# 12-.net
KiCad netlist of a schematic drawn in Altium Designer
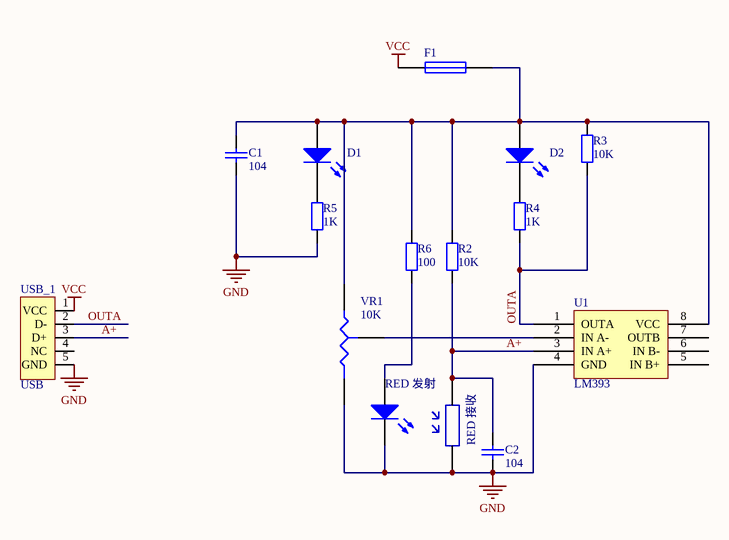
[diagram p0: 12-红外测距及避障原理图.SchDoc]

(export (version "E")
  (design (tool "Eeschema 10.0.6"))
  (components
    (comp (ref "C1")
      (value "104")
      (footprint "0805")
      (description "Capacitor (Semiconductor SIM Model)")
      (fields (field (name "Comment") "Cap Semi") (field (name "PUBLISHER") "Altium Limited"))
      (libsource (lib "Miscellaneous Devices") (part "Cap Semi"))
    )
    (comp (ref "C2")
      (value "104")
      (footprint "0805")
      (description "Capacitor (Semiconductor SIM Model)")
      (fields (field (name "Comment") "Cap Semi") (field (name "PUBLISHER") "Altium Limited"))
      (libsource (lib "Miscellaneous Devices") (part "Cap Semi"))
    )
    (comp (ref "D1")
      (value "LED0")
      (footprint "0805")
      (description "Typical INFRARED GaAs LED")
      (fields (field (name "PUBLISHER") "Altium Limited"))
      (libsource (lib "Miscellaneous Devices") (part "LED0"))
    )
    (comp (ref "D2")
      (value "LED0")
      (footprint "0805")
      (description "Typical INFRARED GaAs LED")
      (fields (field (name "PUBLISHER") "Altium Limited"))
      (libsource (lib "Miscellaneous Devices") (part "LED0"))
    )
    (comp (ref "F1")
      (value "Fuse 1")
      (footprint "Fuse")
      (description "Fuse")
      (fields (field (name "PUBLISHER") "Altium Limited"))
      (libsource (lib "Miscellaneous Devices") (part "Fuse 1"))
    )
    (comp (ref "R2")
      (value "10K")
      (footprint "0805")
      (description "Resistor")
      (fields (field (name "Comment") "Res2") (field (name "PUBLISHER") "Altium Limited"))
      (libsource (lib "Miscellaneous Devices") (part "Res2"))
    )
    (comp (ref "R3")
      (value "10K")
      (footprint "0805")
      (description "Resistor")
      (fields (field (name "Comment") "Res2") (field (name "PUBLISHER") "Altium Limited"))
      (libsource (lib "Miscellaneous Devices") (part "Res2"))
    )
    (comp (ref "R4")
      (value "1K")
      (footprint "0805")
      (description "Resistor")
      (fields (field (name "Comment") "Res2") (field (name "PUBLISHER") "Altium Limited"))
      (libsource (lib "Miscellaneous Devices") (part "Res2"))
    )
    (comp (ref "R5")
      (value "1K")
      (footprint "0805")
      (description "Resistor")
      (fields (field (name "Comment") "Res2") (field (name "PUBLISHER") "Altium Limited"))
      (libsource (lib "Miscellaneous Devices") (part "Res2"))
    )
    (comp (ref "R6")
      (value "100")
      (footprint "0805")
      (description "Resistor")
      (fields (field (name "Comment") "Res2") (field (name "PUBLISHER") "Altium Limited"))
      (libsource (lib "Miscellaneous Devices") (part "Res2"))
    )
    (comp (ref "RED 发射")
      (value "LED0")
      (footprint "LED")
      (description "Typical INFRARED GaAs LED")
      (fields (field (name "PUBLISHER") "Altium Limited"))
      (libsource (lib "Miscellaneous Devices") (part "LED0"))
    )
    (comp (ref "RED 接收") (value "light_resistor") (footprint "LED") (libsource (lib "原理图库") (part "light")))
    (comp (ref "U1") (value "LM393") (footprint "SOP-8") (libsource (lib "原理图库") (part "LM393")))
    (comp (ref "USB_1") (value "USB") (footprint "USB/SM0.8-6H5") (libsource (lib "原理图库") (part "USB5")))
    (comp (ref "VR1")
      (value "10K")
      (footprint "VR")
      (description "Tapped Resistor")
      (fields (field (name "Comment") "Res Tap") (field (name "PUBLISHER") "Altium Limited"))
      (libsource (lib "Miscellaneous Devices") (part "Res Tap"))
    )
  )
  (nets
    (net (code "1") (name "/A+") (class "Default")
      (node (ref "C2") (pin "2") (pinfunction "2_2") (pintype "passive"))
      (node (ref "R2") (pin "1") (pinfunction "1_1") (pintype "passive"))
      (node (ref "RED 接收") (pin "1") (pinfunction "1_1") (pintype "passive"))
      (node (ref "U1") (pin "3") (pinfunction "IN_A+_3") (pintype "passive"))
      (node (ref "USB_1") (pin "3") (pinfunction "D+_3") (pintype "passive"))
    )
    (net (code "2") (name "/OUTA") (class "Default")
      (node (ref "R3") (pin "1") (pinfunction "1_1") (pintype "passive"))
      (node (ref "R4") (pin "1") (pinfunction "1_1") (pintype "passive"))
      (node (ref "U1") (pin "1") (pinfunction "OUTA_1") (pintype "passive"))
      (node (ref "USB_1") (pin "2") (pinfunction "D-_2") (pintype "passive"))
    )
    (net (code "3") (name "GND") (class "Default")
      (node (ref "C1") (pin "1") (pinfunction "1_1") (pintype "passive"))
      (node (ref "C2") (pin "1") (pinfunction "1_1") (pintype "passive"))
      (node (ref "R5") (pin "1") (pinfunction "1_1") (pintype "passive"))
      (node (ref "RED 发射") (pin "2") (pinfunction "K_2") (pintype "passive"))
      (node (ref "RED 接收") (pin "2") (pinfunction "2_2") (pintype "passive"))
      (node (ref "U1") (pin "4") (pinfunction "GND_4") (pintype "passive"))
      (node (ref "USB_1") (pin "5") (pinfunction "GND_5") (pintype "passive"))
      (node (ref "VR1") (pin "2") (pinfunction "B_2") (pintype "passive"))
    )
    (net (code "4") (name "Net-(D1-A)") (class "Default")
      (node (ref "C1") (pin "2") (pinfunction "2_2") (pintype "passive"))
      (node (ref "D1") (pin "1") (pinfunction "A_1") (pintype "passive"))
      (node (ref "D2") (pin "1") (pinfunction "A_1") (pintype "passive"))
      (node (ref "F1") (pin "1") (pinfunction "1_1") (pintype "passive"))
      (node (ref "R2") (pin "2") (pinfunction "2_2") (pintype "passive"))
      (node (ref "R3") (pin "2") (pinfunction "2_2") (pintype "passive"))
      (node (ref "R6") (pin "2") (pinfunction "2_2") (pintype "passive"))
      (node (ref "U1") (pin "8") (pinfunction "VCC_8") (pintype "passive"))
      (node (ref "VR1") (pin "1") (pinfunction "A_1") (pintype "passive"))
    )
    (net (code "5") (name "Net-(D1-K)") (class "Default")
      (node (ref "D1") (pin "2") (pinfunction "K_2") (pintype "passive"))
      (node (ref "R5") (pin "2") (pinfunction "2_2") (pintype "passive"))
    )
    (net (code "6") (name "Net-(D2-K)") (class "Default")
      (node (ref "D2") (pin "2") (pinfunction "K_2") (pintype "passive"))
      (node (ref "R4") (pin "2") (pinfunction "2_2") (pintype "passive"))
    )
    (net (code "7") (name "Net-(RED 发射-A)") (class "Default")
      (node (ref "R6") (pin "1") (pinfunction "1_1") (pintype "passive"))
      (node (ref "RED 发射") (pin "1") (pinfunction "A_1") (pintype "passive"))
    )
    (net (code "8") (name "Net-(U1-IN_A-)") (class "Default")
      (node (ref "U1") (pin "2") (pinfunction "IN_A-_2") (pintype "passive"))
      (node (ref "VR1") (pin "3") (pinfunction "TAP_3") (pintype "passive"))
    )
    (net (code "9") (name "VCC") (class "Default")
      (node (ref "F1") (pin "2") (pinfunction "2_2") (pintype "passive"))
      (node (ref "USB_1") (pin "1") (pinfunction "VCC_1") (pintype "passive"))
    )
    (net (code "10") (name "unconnected-(U1-IN_B+-Pad5)") (class "Default")
      (node (ref "U1") (pin "5") (pinfunction "IN_B+_5") (pintype "passive"))
    )
    (net (code "11") (name "unconnected-(U1-IN_B--Pad6)") (class "Default")
      (node (ref "U1") (pin "6") (pinfunction "IN_B-_6") (pintype "passive"))
    )
    (net (code "12") (name "unconnected-(U1-OUTB-Pad7)") (class "Default")
      (node (ref "U1") (pin "7") (pinfunction "OUTB_7") (pintype "passive"))
    )
    (net (code "13") (name "unconnected-(USB_1-NC-Pad4)") (class "Default")
      (node (ref "USB_1") (pin "4") (pinfunction "NC_4") (pintype "passive"))
    )
  )
)
